# motors_motherBoard.net
KiCad netlist of a schematic drawn in EAGLE
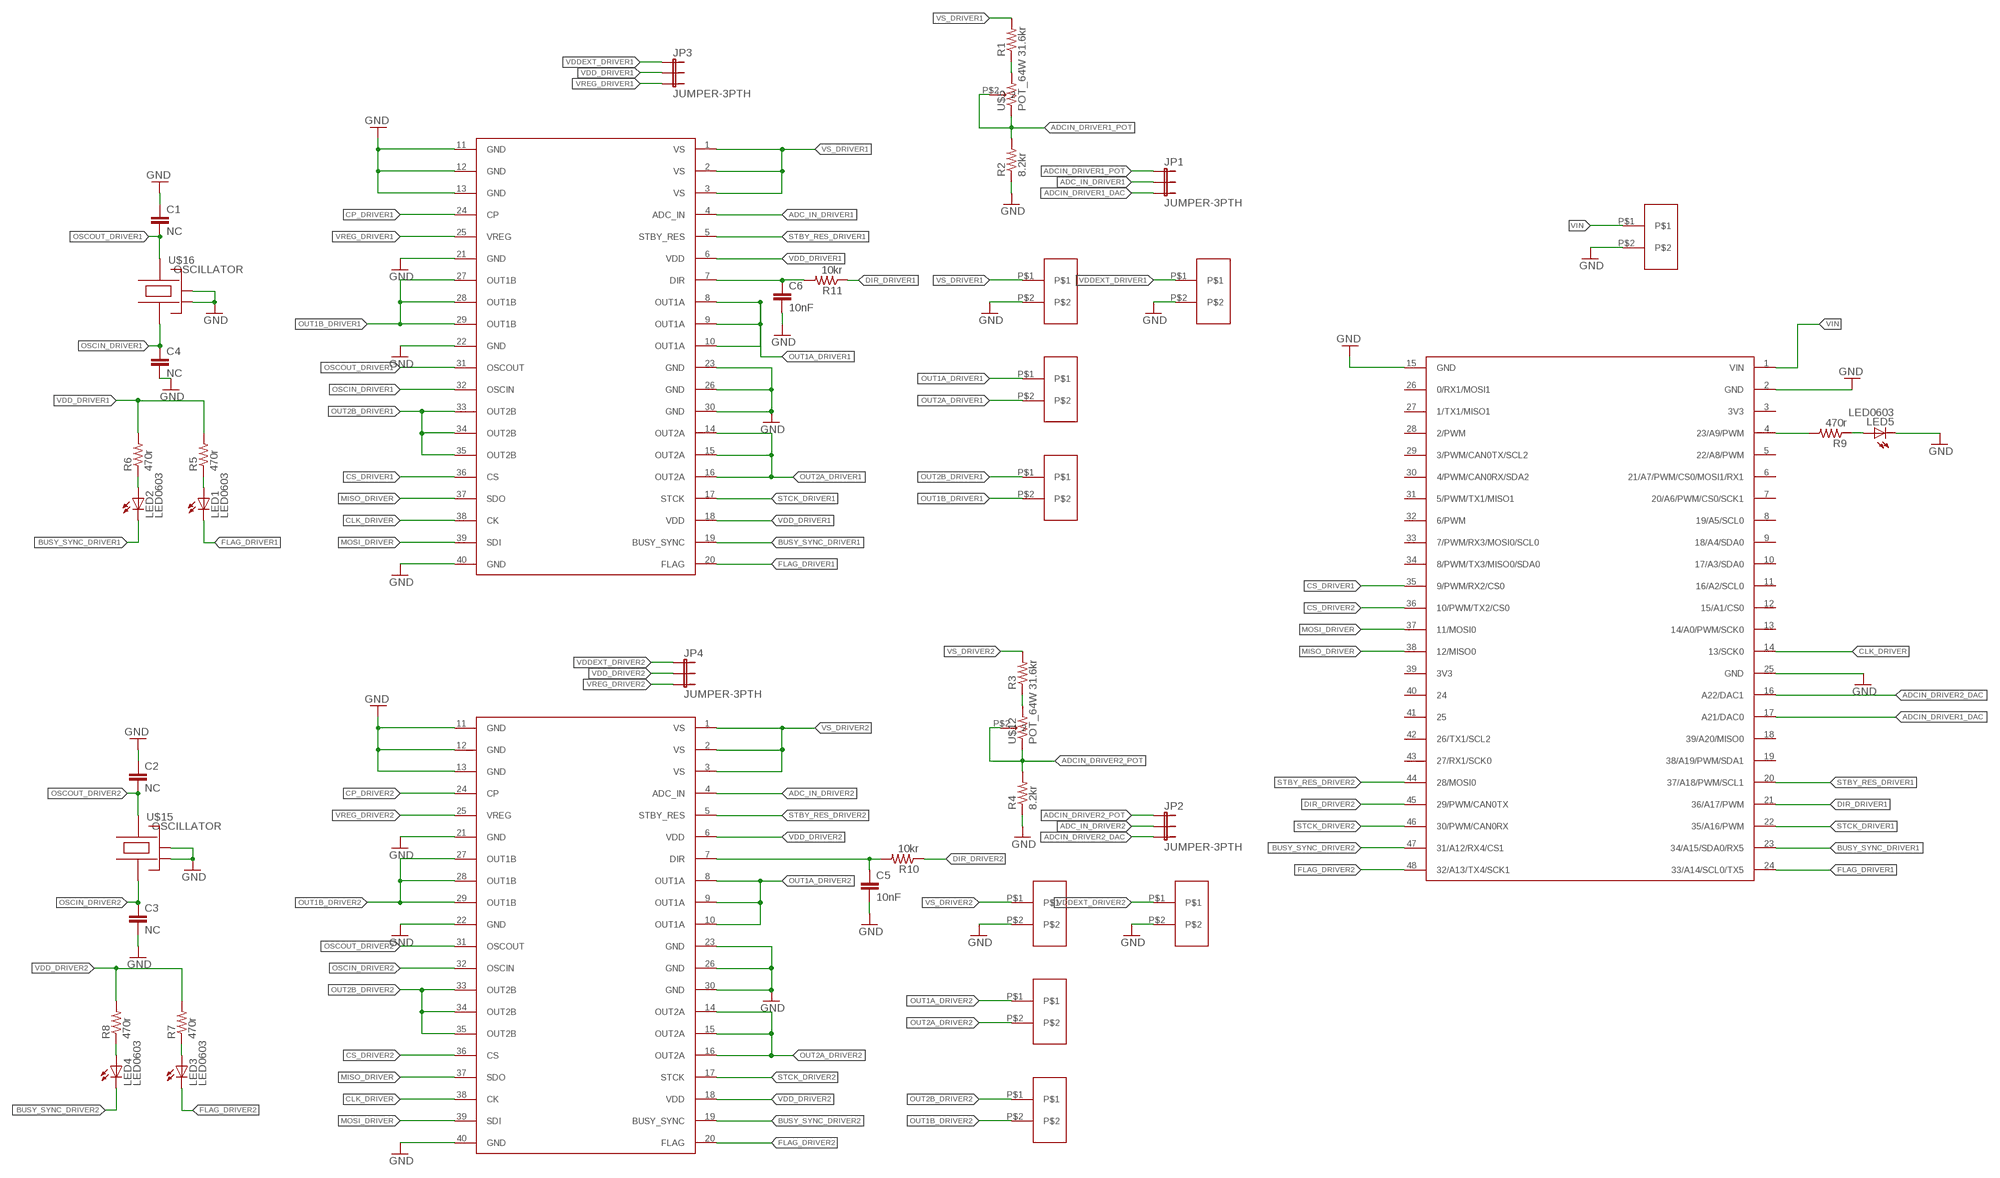
[diagram p0: schematic, sheet 1]

(export (version "E")
  (design (tool "Eeschema 10.0.6"))
  (components
    (comp (ref "C1")
      (value "NC")
      (footprint "eagle-import:0603-CAP")
      (libsource (lib "eagle-import") (part "CAP0603"))
    )
    (comp (ref "C2")
      (value "NC")
      (footprint "eagle-import:0603-CAP")
      (libsource (lib "eagle-import") (part "CAP0603"))
    )
    (comp (ref "C3")
      (value "NC")
      (footprint "eagle-import:0603-CAP")
      (libsource (lib "eagle-import") (part "CAP0603"))
    )
    (comp (ref "C4")
      (value "NC")
      (footprint "eagle-import:0603-CAP")
      (libsource (lib "eagle-import") (part "CAP0603"))
    )
    (comp (ref "C5")
      (value "10nF")
      (footprint "eagle-import:0603-CAP")
      (libsource (lib "eagle-import") (part "CAP0603"))
    )
    (comp (ref "C6")
      (value "10nF")
      (footprint "eagle-import:0603-CAP")
      (libsource (lib "eagle-import") (part "CAP0603"))
    )
    (comp (ref "JP1")
      (value "JUMPER-3PTH")
      (footprint "eagle-import:1X03")
      (libsource (lib "eagle-import") (part "JUMPER-3PTH"))
    )
    (comp (ref "JP2")
      (value "JUMPER-3PTH")
      (footprint "eagle-import:1X03")
      (libsource (lib "eagle-import") (part "JUMPER-3PTH"))
    )
    (comp (ref "JP3")
      (value "JUMPER-3PTH")
      (footprint "eagle-import:1X03")
      (libsource (lib "eagle-import") (part "JUMPER-3PTH"))
    )
    (comp (ref "JP4")
      (value "JUMPER-3PTH")
      (footprint "eagle-import:1X03")
      (libsource (lib "eagle-import") (part "JUMPER-3PTH"))
    )
    (comp (ref "LED1")
      (value "LED0603")
      (footprint "eagle-import:0603-LED")
      (libsource (lib "eagle-import") (part "LED0603"))
    )
    (comp (ref "LED2")
      (value "LED0603")
      (footprint "eagle-import:0603-LED")
      (libsource (lib "eagle-import") (part "LED0603"))
    )
    (comp (ref "LED3")
      (value "LED0603")
      (footprint "eagle-import:0603-LED")
      (libsource (lib "eagle-import") (part "LED0603"))
    )
    (comp (ref "LED4")
      (value "LED0603")
      (footprint "eagle-import:0603-LED")
      (libsource (lib "eagle-import") (part "LED0603"))
    )
    (comp (ref "LED5")
      (value "LED0603")
      (footprint "eagle-import:0603-LED")
      (libsource (lib "eagle-import") (part "LED0603"))
    )
    (comp (ref "R1")
      (value "31.6kr")
      (footprint "eagle-import:0603-RES")
      (libsource (lib "eagle-import") (part "RESISTOR0603-RES"))
    )
    (comp (ref "R2")
      (value "8.2kr")
      (footprint "eagle-import:0603-RES")
      (libsource (lib "eagle-import") (part "RESISTOR0603-RES"))
    )
    (comp (ref "R3")
      (value "31.6kr")
      (footprint "eagle-import:0603-RES")
      (libsource (lib "eagle-import") (part "RESISTOR0603-RES"))
    )
    (comp (ref "R4")
      (value "8.2kr")
      (footprint "eagle-import:0603-RES")
      (libsource (lib "eagle-import") (part "RESISTOR0603-RES"))
    )
    (comp (ref "R5")
      (value "470r")
      (footprint "eagle-import:0603-RES")
      (libsource (lib "eagle-import") (part "RESISTOR0603-RES"))
    )
    (comp (ref "R6")
      (value "470r")
      (footprint "eagle-import:0603-RES")
      (libsource (lib "eagle-import") (part "RESISTOR0603-RES"))
    )
    (comp (ref "R7")
      (value "470r")
      (footprint "eagle-import:0603-RES")
      (libsource (lib "eagle-import") (part "RESISTOR0603-RES"))
    )
    (comp (ref "R8")
      (value "470r")
      (footprint "eagle-import:0603-RES")
      (libsource (lib "eagle-import") (part "RESISTOR0603-RES"))
    )
    (comp (ref "R9")
      (value "470r")
      (footprint "eagle-import:0603-RES")
      (libsource (lib "eagle-import") (part "RESISTOR0603-RES"))
    )
    (comp (ref "R10")
      (value "10kr")
      (footprint "eagle-import:0603-RES")
      (libsource (lib "eagle-import") (part "RESISTOR0603-RES"))
    )
    (comp (ref "R11")
      (value "10kr")
      (footprint "eagle-import:0603-RES")
      (libsource (lib "eagle-import") (part "RESISTOR0603-RES"))
    )
    (comp (ref "U$1")
      (value "MOTORDRIVER_BASE_ADAPTER")
      (footprint "eagle-import:MOTORDRIVER_BASE_ADAPTER")
      (libsource (lib "eagle-import") (part "MOTORDRIVER_BASE_ADAPTER"))
    )
    (comp (ref "U$2")
      (value "MOTORDRIVER_BASE_ADAPTER")
      (footprint "eagle-import:MOTORDRIVER_BASE_ADAPTER")
      (libsource (lib "eagle-import") (part "MOTORDRIVER_BASE_ADAPTER"))
    )
    (comp (ref "U$3")
      (value "TEENSY_BASE_ADAPTER")
      (footprint "eagle-import:TEENSY_BASE_ADAPTER")
      (libsource (lib "eagle-import") (part "TEENSY_BASE_ADAPTER"))
    )
    (comp (ref "U$4")
      (value "SCREW_CON_2POLES")
      (footprint "eagle-import:SCREW_CON_2POLES")
      (libsource (lib "eagle-import") (part "SCREW_CON_2POLES"))
    )
    (comp (ref "U$5")
      (value "POT_64W")
      (footprint "eagle-import:POT_64W")
      (libsource (lib "eagle-import") (part "POT_64W"))
    )
    (comp (ref "U$6")
      (value "SCREW_CON_2POLES")
      (footprint "eagle-import:SCREW_CON_2POLES")
      (libsource (lib "eagle-import") (part "SCREW_CON_2POLES"))
    )
    (comp (ref "U$7")
      (value "SCREW_CON_2POLES")
      (footprint "eagle-import:SCREW_CON_2POLES")
      (libsource (lib "eagle-import") (part "SCREW_CON_2POLES"))
    )
    (comp (ref "U$8")
      (value "SCREW_CON_2POLES")
      (footprint "eagle-import:SCREW_CON_2POLES")
      (libsource (lib "eagle-import") (part "SCREW_CON_2POLES"))
    )
    (comp (ref "U$9")
      (value "SCREW_CON_2POLES")
      (footprint "eagle-import:SCREW_CON_2POLES")
      (libsource (lib "eagle-import") (part "SCREW_CON_2POLES"))
    )
    (comp (ref "U$10")
      (value "SCREW_CON_2POLES")
      (footprint "eagle-import:SCREW_CON_2POLES")
      (libsource (lib "eagle-import") (part "SCREW_CON_2POLES"))
    )
    (comp (ref "U$11")
      (value "SCREW_CON_2POLES")
      (footprint "eagle-import:SCREW_CON_2POLES")
      (libsource (lib "eagle-import") (part "SCREW_CON_2POLES"))
    )
    (comp (ref "U$12")
      (value "POT_64W")
      (footprint "eagle-import:POT_64W")
      (libsource (lib "eagle-import") (part "POT_64W"))
    )
    (comp (ref "U$13")
      (value "SCREW_CON_2POLES")
      (footprint "eagle-import:SCREW_CON_2POLES")
      (libsource (lib "eagle-import") (part "SCREW_CON_2POLES"))
    )
    (comp (ref "U$14")
      (value "SCREW_CON_2POLES")
      (footprint "eagle-import:SCREW_CON_2POLES")
      (libsource (lib "eagle-import") (part "SCREW_CON_2POLES"))
    )
    (comp (ref "U$15")
      (value "OSCILLATOR")
      (footprint "eagle-import:OSCILLATOR_3.2X2.5")
      (libsource (lib "eagle-import") (part "OSCILLATOR"))
    )
    (comp (ref "U$16")
      (value "OSCILLATOR")
      (footprint "eagle-import:OSCILLATOR_3.2X2.5")
      (libsource (lib "eagle-import") (part "OSCILLATOR"))
    )
  )
  (nets
    (net (code "1") (name "ADCIN_DRIVER1_DAC") (class "Default")
      (node (ref "JP1") (pin "3") (pinfunction "3_3") (pintype "passive"))
      (node (ref "U$3") (pin "17") (pinfunction "A21/DAC0_17") (pintype "bidirectional"))
    )
    (net (code "2") (name "ADCIN_DRIVER1_POT") (class "Default")
      (node (ref "JP1") (pin "1") (pinfunction "1_1") (pintype "passive"))
      (node (ref "R2") (pin "2") (pinfunction "2_2") (pintype "passive"))
      (node (ref "U$5") (pin "P$1") (pinfunction "1_P$1") (pintype "passive"))
      (node (ref "U$5") (pin "P$2") (pinfunction "2_P$2") (pintype "bidirectional"))
    )
    (net (code "3") (name "ADCIN_DRIVER2_DAC") (class "Default")
      (node (ref "JP2") (pin "3") (pinfunction "3_3") (pintype "passive"))
      (node (ref "U$3") (pin "16") (pinfunction "A22/DAC1_16") (pintype "bidirectional"))
    )
    (net (code "4") (name "ADCIN_DRIVER2_POT") (class "Default")
      (node (ref "JP2") (pin "1") (pinfunction "1_1") (pintype "passive"))
      (node (ref "R4") (pin "2") (pinfunction "2_2") (pintype "passive"))
      (node (ref "U$12") (pin "P$1") (pinfunction "1_P$1") (pintype "passive"))
      (node (ref "U$12") (pin "P$2") (pinfunction "2_P$2") (pintype "bidirectional"))
    )
    (net (code "5") (name "ADC_IN_DRIVER1") (class "Default")
      (node (ref "JP1") (pin "2") (pinfunction "2_2") (pintype "passive"))
      (node (ref "U$2") (pin "4") (pinfunction "ADC_IN_4") (pintype "bidirectional"))
    )
    (net (code "6") (name "ADC_IN_DRIVER2") (class "Default")
      (node (ref "JP2") (pin "2") (pinfunction "2_2") (pintype "passive"))
      (node (ref "U$1") (pin "4") (pinfunction "ADC_IN_4") (pintype "bidirectional"))
    )
    (net (code "7") (name "BUSY_SYNC_DRIVER1") (class "Default")
      (node (ref "LED2") (pin "C") (pinfunction "C_C") (pintype "passive"))
      (node (ref "U$2") (pin "19") (pinfunction "BUSY_SYNC_19") (pintype "bidirectional"))
      (node (ref "U$3") (pin "23") (pinfunction "34/A15/SDA0/RX5_23") (pintype "bidirectional"))
    )
    (net (code "8") (name "BUSY_SYNC_DRIVER2") (class "Default")
      (node (ref "LED4") (pin "C") (pinfunction "C_C") (pintype "passive"))
      (node (ref "U$1") (pin "19") (pinfunction "BUSY_SYNC_19") (pintype "bidirectional"))
      (node (ref "U$3") (pin "47") (pinfunction "31/A12/RX4/CS1_47") (pintype "bidirectional"))
    )
    (net (code "9") (name "CLK_DRIVER") (class "Default")
      (node (ref "U$1") (pin "38") (pinfunction "CK_38") (pintype "bidirectional"))
      (node (ref "U$2") (pin "38") (pinfunction "CK_38") (pintype "bidirectional"))
      (node (ref "U$3") (pin "14") (pinfunction "13/SCK0_14") (pintype "bidirectional"))
    )
    (net (code "10") (name "CP_DRIVER1") (class "Default")
      (node (ref "U$2") (pin "24") (pinfunction "CP_24") (pintype "bidirectional"))
    )
    (net (code "11") (name "CP_DRIVER2") (class "Default")
      (node (ref "U$1") (pin "24") (pinfunction "CP_24") (pintype "bidirectional"))
    )
    (net (code "12") (name "CS_DRIVER1") (class "Default")
      (node (ref "U$2") (pin "36") (pinfunction "CS_36") (pintype "bidirectional"))
      (node (ref "U$3") (pin "35") (pinfunction "9/PWM/RX2/CS0_35") (pintype "bidirectional"))
    )
    (net (code "13") (name "CS_DRIVER2") (class "Default")
      (node (ref "U$1") (pin "36") (pinfunction "CS_36") (pintype "bidirectional"))
      (node (ref "U$3") (pin "36") (pinfunction "10/PWM/TX2/CS0_36") (pintype "bidirectional"))
    )
    (net (code "14") (name "DIR_DRIVER1") (class "Default")
      (node (ref "R11") (pin "1") (pinfunction "1_1") (pintype "passive"))
      (node (ref "U$3") (pin "21") (pinfunction "36/A17/PWM_21") (pintype "bidirectional"))
    )
    (net (code "15") (name "DIR_DRIVER2") (class "Default")
      (node (ref "R10") (pin "1") (pinfunction "1_1") (pintype "passive"))
      (node (ref "U$3") (pin "45") (pinfunction "29/PWM/CAN0TX_45") (pintype "bidirectional"))
    )
    (net (code "16") (name "FLAG_DRIVER1") (class "Default")
      (node (ref "LED1") (pin "C") (pinfunction "C_C") (pintype "passive"))
      (node (ref "U$2") (pin "20") (pinfunction "FLAG_20") (pintype "bidirectional"))
      (node (ref "U$3") (pin "24") (pinfunction "33/A14/SCL0/TX5_24") (pintype "bidirectional"))
    )
    (net (code "17") (name "FLAG_DRIVER2") (class "Default")
      (node (ref "LED3") (pin "C") (pinfunction "C_C") (pintype "passive"))
      (node (ref "U$1") (pin "20") (pinfunction "FLAG_20") (pintype "bidirectional"))
      (node (ref "U$3") (pin "48") (pinfunction "32/A13/TX4/SCK1_48") (pintype "bidirectional"))
    )
    (net (code "18") (name "GND") (class "Default")
      (node (ref "C1") (pin "P$1") (pinfunction "1_P$1") (pintype "passive"))
      (node (ref "C2") (pin "P$1") (pinfunction "1_P$1") (pintype "passive"))
      (node (ref "C3") (pin "P$2") (pinfunction "2_P$2") (pintype "passive"))
      (node (ref "C4") (pin "P$2") (pinfunction "2_P$2") (pintype "passive"))
      (node (ref "C5") (pin "P$2") (pinfunction "2_P$2") (pintype "passive"))
      (node (ref "C6") (pin "P$2") (pinfunction "2_P$2") (pintype "passive"))
      (node (ref "LED5") (pin "C") (pinfunction "C_C") (pintype "passive"))
      (node (ref "R2") (pin "1") (pinfunction "1_1") (pintype "passive"))
      (node (ref "R4") (pin "1") (pinfunction "1_1") (pintype "passive"))
      (node (ref "U$1") (pin "11") (pinfunction "GND_11") (pintype "bidirectional"))
      (node (ref "U$1") (pin "12") (pinfunction "GND_12") (pintype "bidirectional"))
      (node (ref "U$1") (pin "13") (pinfunction "GND_13") (pintype "bidirectional"))
      (node (ref "U$1") (pin "21") (pinfunction "GND_21") (pintype "bidirectional"))
      (node (ref "U$1") (pin "22") (pinfunction "GND_22") (pintype "bidirectional"))
      (node (ref "U$1") (pin "23") (pinfunction "GND_23") (pintype "bidirectional"))
      (node (ref "U$1") (pin "26") (pinfunction "GND_26") (pintype "bidirectional"))
      (node (ref "U$1") (pin "30") (pinfunction "GND_30") (pintype "bidirectional"))
      (node (ref "U$1") (pin "40") (pinfunction "GND_40") (pintype "bidirectional"))
      (node (ref "U$11") (pin "P$2") (pinfunction "P$2_P$2") (pintype "bidirectional"))
      (node (ref "U$13") (pin "P$2") (pinfunction "P$2_P$2") (pintype "bidirectional"))
      (node (ref "U$14") (pin "P$2") (pinfunction "P$2_P$2") (pintype "bidirectional"))
      (node (ref "U$15") (pin "2") (pinfunction "GND_2") (pintype "power_in"))
      (node (ref "U$15") (pin "4") (pinfunction "GND_4") (pintype "power_in"))
      (node (ref "U$16") (pin "2") (pinfunction "GND_2") (pintype "power_in"))
      (node (ref "U$16") (pin "4") (pinfunction "GND_4") (pintype "power_in"))
      (node (ref "U$2") (pin "11") (pinfunction "GND_11") (pintype "bidirectional"))
      (node (ref "U$2") (pin "12") (pinfunction "GND_12") (pintype "bidirectional"))
      (node (ref "U$2") (pin "13") (pinfunction "GND_13") (pintype "bidirectional"))
      (node (ref "U$2") (pin "21") (pinfunction "GND_21") (pintype "bidirectional"))
      (node (ref "U$2") (pin "22") (pinfunction "GND_22") (pintype "bidirectional"))
      (node (ref "U$2") (pin "23") (pinfunction "GND_23") (pintype "bidirectional"))
      (node (ref "U$2") (pin "26") (pinfunction "GND_26") (pintype "bidirectional"))
      (node (ref "U$2") (pin "30") (pinfunction "GND_30") (pintype "bidirectional"))
      (node (ref "U$2") (pin "40") (pinfunction "GND_40") (pintype "bidirectional"))
      (node (ref "U$3") (pin "15") (pinfunction "GND_15") (pintype "bidirectional"))
      (node (ref "U$3") (pin "2") (pinfunction "GND_2") (pintype "bidirectional"))
      (node (ref "U$3") (pin "25") (pinfunction "GND_25") (pintype "bidirectional"))
      (node (ref "U$7") (pin "P$2") (pinfunction "P$2_P$2") (pintype "bidirectional"))
      (node (ref "U$9") (pin "P$2") (pinfunction "P$2_P$2") (pintype "bidirectional"))
    )
    (net (code "19") (name "MISO_DRIVER") (class "Default")
      (node (ref "U$1") (pin "37") (pinfunction "SDO_37") (pintype "bidirectional"))
      (node (ref "U$2") (pin "37") (pinfunction "SDO_37") (pintype "bidirectional"))
      (node (ref "U$3") (pin "38") (pinfunction "12/MISO0_38") (pintype "bidirectional"))
    )
    (net (code "20") (name "MOSI_DRIVER") (class "Default")
      (node (ref "U$1") (pin "39") (pinfunction "SDI_39") (pintype "bidirectional"))
      (node (ref "U$2") (pin "39") (pinfunction "SDI_39") (pintype "bidirectional"))
      (node (ref "U$3") (pin "37") (pinfunction "11/MOSI0_37") (pintype "bidirectional"))
    )
    (net (code "21") (name "Net-(C5-1)") (class "Default")
      (node (ref "C5") (pin "P$1") (pinfunction "1_P$1") (pintype "passive"))
      (node (ref "R10") (pin "2") (pinfunction "2_2") (pintype "passive"))
      (node (ref "U$1") (pin "7") (pinfunction "DIR_7") (pintype "bidirectional"))
    )
    (net (code "22") (name "Net-(C6-1)") (class "Default")
      (node (ref "C6") (pin "P$1") (pinfunction "1_P$1") (pintype "passive"))
      (node (ref "R11") (pin "2") (pinfunction "2_2") (pintype "passive"))
      (node (ref "U$2") (pin "7") (pinfunction "DIR_7") (pintype "bidirectional"))
    )
    (net (code "23") (name "Net-(LED1-PadA)") (class "Default")
      (node (ref "LED1") (pin "A") (pinfunction "A_A") (pintype "passive"))
      (node (ref "R5") (pin "1") (pinfunction "1_1") (pintype "passive"))
    )
    (net (code "24") (name "Net-(LED2-PadA)") (class "Default")
      (node (ref "LED2") (pin "A") (pinfunction "A_A") (pintype "passive"))
      (node (ref "R6") (pin "1") (pinfunction "1_1") (pintype "passive"))
    )
    (net (code "25") (name "Net-(LED3-PadA)") (class "Default")
      (node (ref "LED3") (pin "A") (pinfunction "A_A") (pintype "passive"))
      (node (ref "R7") (pin "1") (pinfunction "1_1") (pintype "passive"))
    )
    (net (code "26") (name "Net-(LED4-PadA)") (class "Default")
      (node (ref "LED4") (pin "A") (pinfunction "A_A") (pintype "passive"))
      (node (ref "R8") (pin "1") (pinfunction "1_1") (pintype "passive"))
    )
    (net (code "27") (name "Net-(LED5-PadA)") (class "Default")
      (node (ref "LED5") (pin "A") (pinfunction "A_A") (pintype "passive"))
      (node (ref "R9") (pin "1") (pinfunction "1_1") (pintype "passive"))
    )
    (net (code "28") (name "Net-(U$3-23{slash}A9{slash}PWM)") (class "Default")
      (node (ref "R9") (pin "2") (pinfunction "2_2") (pintype "passive"))
      (node (ref "U$3") (pin "4") (pinfunction "23/A9/PWM_4") (pintype "bidirectional"))
    )
    (net (code "29") (name "Net-(U$5-3)") (class "Default")
      (node (ref "R1") (pin "1") (pinfunction "1_1") (pintype "passive"))
      (node (ref "U$5") (pin "P$3") (pinfunction "3_P$3") (pintype "passive"))
    )
    (net (code "30") (name "Net-(U$12-3)") (class "Default")
      (node (ref "R3") (pin "1") (pinfunction "1_1") (pintype "passive"))
      (node (ref "U$12") (pin "P$3") (pinfunction "3_P$3") (pintype "passive"))
    )
    (net (code "31") (name "OSCIN_DRIVER1") (class "Default")
      (node (ref "C4") (pin "P$1") (pinfunction "1_P$1") (pintype "passive"))
      (node (ref "U$16") (pin "1") (pinfunction "1_1") (pintype "bidirectional"))
      (node (ref "U$2") (pin "32") (pinfunction "OSCIN_32") (pintype "bidirectional"))
    )
    (net (code "32") (name "OSCIN_DRIVER2") (class "Default")
      (node (ref "C3") (pin "P$1") (pinfunction "1_P$1") (pintype "passive"))
      (node (ref "U$1") (pin "32") (pinfunction "OSCIN_32") (pintype "bidirectional"))
      (node (ref "U$15") (pin "1") (pinfunction "1_1") (pintype "bidirectional"))
    )
    (net (code "33") (name "OSCOUT_DRIVER1") (class "Default")
      (node (ref "C1") (pin "P$2") (pinfunction "2_P$2") (pintype "passive"))
      (node (ref "U$16") (pin "3") (pinfunction "3_3") (pintype "bidirectional"))
      (node (ref "U$2") (pin "31") (pinfunction "OSCOUT_31") (pintype "bidirectional"))
    )
    (net (code "34") (name "OSCOUT_DRIVER2") (class "Default")
      (node (ref "C2") (pin "P$2") (pinfunction "2_P$2") (pintype "passive"))
      (node (ref "U$1") (pin "31") (pinfunction "OSCOUT_31") (pintype "bidirectional"))
      (node (ref "U$15") (pin "3") (pinfunction "3_3") (pintype "bidirectional"))
    )
    (net (code "35") (name "OUT1A_DRIVER1") (class "Default")
      (node (ref "U$2") (pin "10") (pinfunction "OUT1A_10") (pintype "bidirectional"))
      (node (ref "U$2") (pin "8") (pinfunction "OUT1A_8") (pintype "bidirectional"))
      (node (ref "U$2") (pin "9") (pinfunction "OUT1A_9") (pintype "bidirectional"))
      (node (ref "U$6") (pin "P$1") (pinfunction "P$1_P$1") (pintype "bidirectional"))
    )
    (net (code "36") (name "OUT1A_DRIVER2") (class "Default")
      (node (ref "U$1") (pin "10") (pinfunction "OUT1A_10") (pintype "bidirectional"))
      (node (ref "U$1") (pin "8") (pinfunction "OUT1A_8") (pintype "bidirectional"))
      (node (ref "U$1") (pin "9") (pinfunction "OUT1A_9") (pintype "bidirectional"))
      (node (ref "U$4") (pin "P$1") (pinfunction "P$1_P$1") (pintype "bidirectional"))
    )
    (net (code "37") (name "OUT1B_DRIVER1") (class "Default")
      (node (ref "U$2") (pin "27") (pinfunction "OUT1B_27") (pintype "bidirectional"))
      (node (ref "U$2") (pin "28") (pinfunction "OUT1B_28") (pintype "bidirectional"))
      (node (ref "U$2") (pin "29") (pinfunction "OUT1B_29") (pintype "bidirectional"))
      (node (ref "U$8") (pin "P$2") (pinfunction "P$2_P$2") (pintype "bidirectional"))
    )
    (net (code "38") (name "OUT1B_DRIVER2") (class "Default")
      (node (ref "U$1") (pin "27") (pinfunction "OUT1B_27") (pintype "bidirectional"))
      (node (ref "U$1") (pin "28") (pinfunction "OUT1B_28") (pintype "bidirectional"))
      (node (ref "U$1") (pin "29") (pinfunction "OUT1B_29") (pintype "bidirectional"))
      (node (ref "U$10") (pin "P$2") (pinfunction "P$2_P$2") (pintype "bidirectional"))
    )
    (net (code "39") (name "OUT2A_DRIVER1") (class "Default")
      (node (ref "U$2") (pin "14") (pinfunction "OUT2A_14") (pintype "bidirectional"))
      (node (ref "U$2") (pin "15") (pinfunction "OUT2A_15") (pintype "bidirectional"))
      (node (ref "U$2") (pin "16") (pinfunction "OUT2A_16") (pintype "bidirectional"))
      (node (ref "U$6") (pin "P$2") (pinfunction "P$2_P$2") (pintype "bidirectional"))
    )
    (net (code "40") (name "OUT2A_DRIVER2") (class "Default")
      (node (ref "U$1") (pin "14") (pinfunction "OUT2A_14") (pintype "bidirectional"))
      (node (ref "U$1") (pin "15") (pinfunction "OUT2A_15") (pintype "bidirectional"))
      (node (ref "U$1") (pin "16") (pinfunction "OUT2A_16") (pintype "bidirectional"))
      (node (ref "U$4") (pin "P$2") (pinfunction "P$2_P$2") (pintype "bidirectional"))
    )
    (net (code "41") (name "OUT2B_DRIVER1") (class "Default")
      (node (ref "U$2") (pin "33") (pinfunction "OUT2B_33") (pintype "bidirectional"))
      (node (ref "U$2") (pin "34") (pinfunction "OUT2B_34") (pintype "bidirectional"))
      (node (ref "U$2") (pin "35") (pinfunction "OUT2B_35") (pintype "bidirectional"))
      (node (ref "U$8") (pin "P$1") (pinfunction "P$1_P$1") (pintype "bidirectional"))
    )
    (net (code "42") (name "OUT2B_DRIVER2") (class "Default")
      (node (ref "U$1") (pin "33") (pinfunction "OUT2B_33") (pintype "bidirectional"))
      (node (ref "U$1") (pin "34") (pinfunction "OUT2B_34") (pintype "bidirectional"))
      (node (ref "U$1") (pin "35") (pinfunction "OUT2B_35") (pintype "bidirectional"))
      (node (ref "U$10") (pin "P$1") (pinfunction "P$1_P$1") (pintype "bidirectional"))
    )
    (net (code "43") (name "STBY_RES_DRIVER1") (class "Default")
      (node (ref "U$2") (pin "5") (pinfunction "STBY_RES_5") (pintype "bidirectional"))
      (node (ref "U$3") (pin "20") (pinfunction "37/A18/PWM/SCL1_20") (pintype "bidirectional"))
    )
    (net (code "44") (name "STBY_RES_DRIVER2") (class "Default")
      (node (ref "U$1") (pin "5") (pinfunction "STBY_RES_5") (pintype "bidirectional"))
      (node (ref "U$3") (pin "44") (pinfunction "28/MOSI0_44") (pintype "bidirectional"))
    )
    (net (code "45") (name "STCK_DRIVER1") (class "Default")
      (node (ref "U$2") (pin "17") (pinfunction "STCK_17") (pintype "bidirectional"))
      (node (ref "U$3") (pin "22") (pinfunction "35/A16/PWM_22") (pintype "bidirectional"))
    )
    (net (code "46") (name "STCK_DRIVER2") (class "Default")
      (node (ref "U$1") (pin "17") (pinfunction "STCK_17") (pintype "bidirectional"))
      (node (ref "U$3") (pin "46") (pinfunction "30/PWM/CAN0RX_46") (pintype "bidirectional"))
    )
    (net (code "47") (name "VDDEXT_DRIVER1") (class "Default")
      (node (ref "JP3") (pin "1") (pinfunction "1_1") (pintype "passive"))
      (node (ref "U$13") (pin "P$1") (pinfunction "P$1_P$1") (pintype "bidirectional"))
    )
    (net (code "48") (name "VDDEXT_DRIVER2") (class "Default")
      (node (ref "JP4") (pin "1") (pinfunction "1_1") (pintype "passive"))
      (node (ref "U$11") (pin "P$1") (pinfunction "P$1_P$1") (pintype "bidirectional"))
    )
    (net (code "49") (name "VDD_DRIVER1") (class "Default")
      (node (ref "JP3") (pin "2") (pinfunction "2_2") (pintype "passive"))
      (node (ref "R5") (pin "2") (pinfunction "2_2") (pintype "passive"))
      (node (ref "R6") (pin "2") (pinfunction "2_2") (pintype "passive"))
      (node (ref "U$2") (pin "18") (pinfunction "VDD_18") (pintype "bidirectional"))
      (node (ref "U$2") (pin "6") (pinfunction "VDD_6") (pintype "bidirectional"))
    )
    (net (code "50") (name "VDD_DRIVER2") (class "Default")
      (node (ref "JP4") (pin "2") (pinfunction "2_2") (pintype "passive"))
      (node (ref "R7") (pin "2") (pinfunction "2_2") (pintype "passive"))
      (node (ref "R8") (pin "2") (pinfunction "2_2") (pintype "passive"))
      (node (ref "U$1") (pin "18") (pinfunction "VDD_18") (pintype "bidirectional"))
      (node (ref "U$1") (pin "6") (pinfunction "VDD_6") (pintype "bidirectional"))
    )
    (net (code "51") (name "VIN") (class "Default")
      (node (ref "U$14") (pin "P$1") (pinfunction "P$1_P$1") (pintype "bidirectional"))
      (node (ref "U$3") (pin "1") (pinfunction "VIN_1") (pintype "bidirectional"))
    )
    (net (code "52") (name "VREG_DRIVER1") (class "Default")
      (node (ref "JP3") (pin "3") (pinfunction "3_3") (pintype "passive"))
      (node (ref "U$2") (pin "25") (pinfunction "VREG_25") (pintype "bidirectional"))
    )
    (net (code "53") (name "VREG_DRIVER2") (class "Default")
      (node (ref "JP4") (pin "3") (pinfunction "3_3") (pintype "passive"))
      (node (ref "U$1") (pin "25") (pinfunction "VREG_25") (pintype "bidirectional"))
    )
    (net (code "54") (name "VS_DRIVER1") (class "Default")
      (node (ref "R1") (pin "2") (pinfunction "2_2") (pintype "passive"))
      (node (ref "U$2") (pin "1") (pinfunction "VS_1") (pintype "bidirectional"))
      (node (ref "U$2") (pin "2") (pinfunction "VS_2") (pintype "bidirectional"))
      (node (ref "U$2") (pin "3") (pinfunction "VS_3") (pintype "bidirectional"))
      (node (ref "U$7") (pin "P$1") (pinfunction "P$1_P$1") (pintype "bidirectional"))
    )
    (net (code "55") (name "VS_DRIVER2") (class "Default")
      (node (ref "R3") (pin "2") (pinfunction "2_2") (pintype "passive"))
      (node (ref "U$1") (pin "1") (pinfunction "VS_1") (pintype "bidirectional"))
      (node (ref "U$1") (pin "2") (pinfunction "VS_2") (pintype "bidirectional"))
      (node (ref "U$1") (pin "3") (pinfunction "VS_3") (pintype "bidirectional"))
      (node (ref "U$9") (pin "P$1") (pinfunction "P$1_P$1") (pintype "bidirectional"))
    )
    (net (code "56") (name "unconnected-(U$3-0{slash}RX1{slash}MOSI1-Pad26)") (class "Default")
      (node (ref "U$3") (pin "26") (pinfunction "0/RX1/MOSI1_26") (pintype "bidirectional"))
    )
    (net (code "57") (name "unconnected-(U$3-1{slash}TX1{slash}MISO1-Pad27)") (class "Default")
      (node (ref "U$3") (pin "27") (pinfunction "1/TX1/MISO1_27") (pintype "bidirectional"))
    )
    (net (code "58") (name "unconnected-(U$3-2{slash}PWM-Pad28)") (class "Default")
      (node (ref "U$3") (pin "28") (pinfunction "2/PWM_28") (pintype "bidirectional"))
    )
    (net (code "59") (name "unconnected-(U$3-3V3-Pad3)") (class "Default")
      (node (ref "U$3") (pin "3") (pinfunction "3V3_3") (pintype "bidirectional"))
    )
    (net (code "60") (name "unconnected-(U$3-3V3-Pad39)") (class "Default")
      (node (ref "U$3") (pin "39") (pinfunction "3V3_39") (pintype "bidirectional"))
    )
    (net (code "61") (name "unconnected-(U$3-3{slash}PWM{slash}CAN0TX{slash}SCL2-Pad29)") (class "Default")
      (node (ref "U$3") (pin "29") (pinfunction "3/PWM/CAN0TX/SCL2_29") (pintype "bidirectional"))
    )
    (net (code "62") (name "unconnected-(U$3-4{slash}PWM{slash}CAN0RX{slash}SDA2-Pad30)") (class "Default")
      (node (ref "U$3") (pin "30") (pinfunction "4/PWM/CAN0RX/SDA2_30") (pintype "bidirectional"))
    )
    (net (code "63") (name "unconnected-(U$3-5{slash}PWM{slash}TX1{slash}MISO1-Pad31)") (class "Default")
      (node (ref "U$3") (pin "31") (pinfunction "5/PWM/TX1/MISO1_31") (pintype "bidirectional"))
    )
    (net (code "64") (name "unconnected-(U$3-6{slash}PWM-Pad32)") (class "Default")
      (node (ref "U$3") (pin "32") (pinfunction "6/PWM_32") (pintype "bidirectional"))
    )
    (net (code "65") (name "unconnected-(U$3-7{slash}PWM{slash}RX3{slash}MOSI0{slash}SCL0-Pad33)") (class "Default")
      (node (ref "U$3") (pin "33") (pinfunction "7/PWM/RX3/MOSI0/SCL0_33") (pintype "bidirectional"))
    )
    (net (code "66") (name "unconnected-(U$3-8{slash}PWM{slash}TX3{slash}MISO0{slash}SDA0-Pad34)") (class "Default")
      (node (ref "U$3") (pin "34") (pinfunction "8/PWM/TX3/MISO0/SDA0_34") (pintype "bidirectional"))
    )
    (net (code "67") (name "unconnected-(U$3-14{slash}A0{slash}PWM{slash}SCK0-Pad13)") (class "Default")
      (node (ref "U$3") (pin "13") (pinfunction "14/A0/PWM/SCK0_13") (pintype "bidirectional"))
    )
    (net (code "68") (name "unconnected-(U$3-15{slash}A1{slash}CS0-Pad12)") (class "Default")
      (node (ref "U$3") (pin "12") (pinfunction "15/A1/CS0_12") (pintype "bidirectional"))
    )
    (net (code "69") (name "unconnected-(U$3-16{slash}A2{slash}SCL0-Pad11)") (class "Default")
      (node (ref "U$3") (pin "11") (pinfunction "16/A2/SCL0_11") (pintype "bidirectional"))
    )
    (net (code "70") (name "unconnected-(U$3-17{slash}A3{slash}SDA0-Pad10)") (class "Default")
      (node (ref "U$3") (pin "10") (pinfunction "17/A3/SDA0_10") (pintype "bidirectional"))
    )
    (net (code "71") (name "unconnected-(U$3-18{slash}A4{slash}SDA0-Pad9)") (class "Default")
      (node (ref "U$3") (pin "9") (pinfunction "18/A4/SDA0_9") (pintype "bidirectional"))
    )
    (net (code "72") (name "unconnected-(U$3-19{slash}A5{slash}SCL0-Pad8)") (class "Default")
      (node (ref "U$3") (pin "8") (pinfunction "19/A5/SCL0_8") (pintype "bidirectional"))
    )
    (net (code "73") (name "unconnected-(U$3-20{slash}A6{slash}PWM{slash}CS0{slash}SCK1-Pad7)") (class "Default")
      (node (ref "U$3") (pin "7") (pinfunction "20/A6/PWM/CS0/SCK1_7") (pintype "bidirectional"))
    )
    (net (code "74") (name "unconnected-(U$3-21{slash}A7{slash}PWM{slash}CS0{slash}MOSI1{slash}RX1-Pad6)") (class "Default")
      (node (ref "U$3") (pin "6") (pinfunction "21/A7/PWM/CS0/MOSI1/RX1_6") (pintype "bidirectional"))
    )
    (net (code "75") (name "unconnected-(U$3-22{slash}A8{slash}PWM-Pad5)") (class "Default")
      (node (ref "U$3") (pin "5") (pinfunction "22/A8/PWM_5") (pintype "bidirectional"))
    )
    (net (code "76") (name "unconnected-(U$3-24-Pad40)") (class "Default")
      (node (ref "U$3") (pin "40") (pinfunction "24_40") (pintype "bidirectional"))
    )
    (net (code "77") (name "unconnected-(U$3-25-Pad41)") (class "Default")
      (node (ref "U$3") (pin "41") (pinfunction "25_41") (pintype "bidirectional"))
    )
    (net (code "78") (name "unconnected-(U$3-26{slash}TX1{slash}SCL2-Pad42)") (class "Default")
      (node (ref "U$3") (pin "42") (pinfunction "26/TX1/SCL2_42") (pintype "bidirectional"))
    )
    (net (code "79") (name "unconnected-(U$3-27{slash}RX1{slash}SCK0-Pad43)") (class "Default")
      (node (ref "U$3") (pin "43") (pinfunction "27/RX1/SCK0_43") (pintype "bidirectional"))
    )
    (net (code "80") (name "unconnected-(U$3-38{slash}A19{slash}PWM{slash}SDA1-Pad19)") (class "Default")
      (node (ref "U$3") (pin "19") (pinfunction "38/A19/PWM/SDA1_19") (pintype "bidirectional"))
    )
    (net (code "81") (name "unconnected-(U$3-39{slash}A20{slash}MISO0-Pad18)") (class "Default")
      (node (ref "U$3") (pin "18") (pinfunction "39/A20/MISO0_18") (pintype "bidirectional"))
    )
  )
)
